# TC364_MainBoard_Core_V2_0.net
KiCad netlist of a schematic drawn in Altium Designer
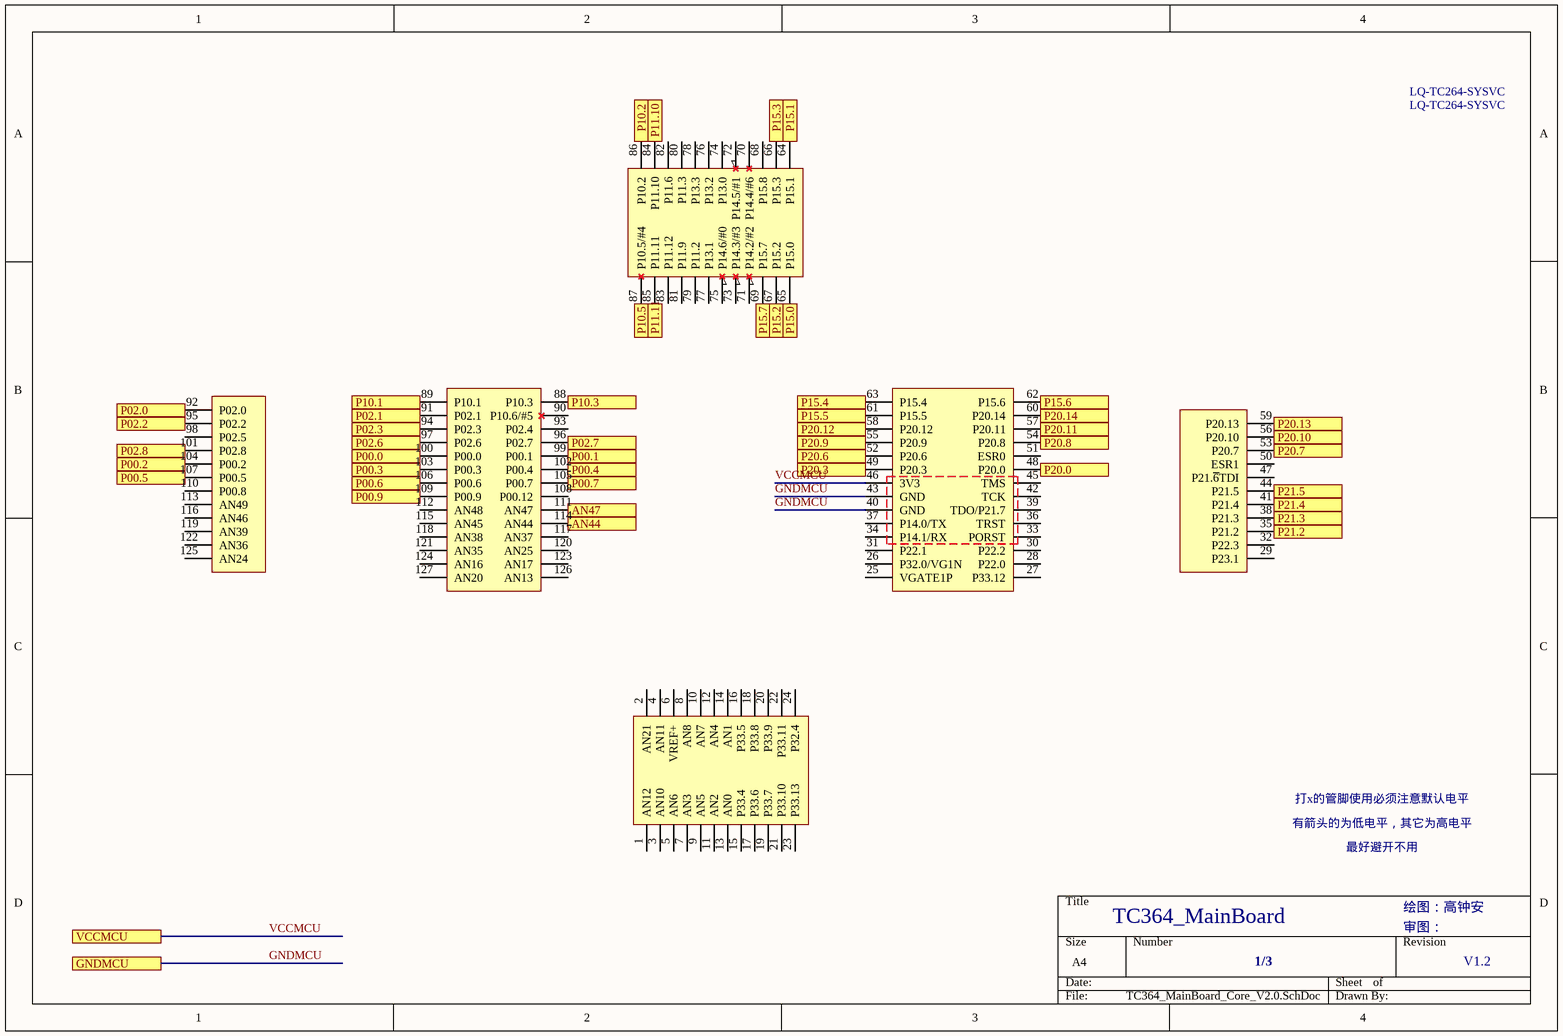
[diagram p0: TC364_MainBoard_Core_V2.0.SchDoc]

(export (version "E")
  (design (tool "Eeschema 10.0.6"))
  (components
    (comp (ref "LQ-TC264-SYSVC")
      (value "LQ-TC264-SYSVC")
      (footprint "TC364V1.2")
      (libsource (lib "LQ-TC264-SYSVC封装") (part "LQ-TC264-SYSVC"))
    )
  )
  (nets
    (net (code "1") (name "/AN44") (class "Default")
      (node (ref "LQ-TC264-SYSVC") (pin "114") (pinfunction "AN44_114") (pintype "passive"))
    )
    (net (code "2") (name "/AN47") (class "Default")
      (node (ref "LQ-TC264-SYSVC") (pin "111") (pinfunction "AN47_111") (pintype "passive"))
    )
    (net (code "3") (name "/GNDMCU") (class "Default")
      (node (ref "LQ-TC264-SYSVC") (pin "40") (pinfunction "GND_40") (pintype "passive"))
      (node (ref "LQ-TC264-SYSVC") (pin "43") (pinfunction "GND_43") (pintype "passive"))
    )
    (net (code "4") (name "/P00.0") (class "Default")
      (node (ref "LQ-TC264-SYSVC") (pin "100") (pinfunction "P00.0_100") (pintype "passive"))
    )
    (net (code "5") (name "/P00.1") (class "Default")
      (node (ref "LQ-TC264-SYSVC") (pin "99") (pinfunction "P00.1_99") (pintype "passive"))
    )
    (net (code "6") (name "/P00.2") (class "Default")
      (node (ref "LQ-TC264-SYSVC") (pin "104") (pinfunction "P00.2_104") (pintype "passive"))
    )
    (net (code "7") (name "/P00.3") (class "Default")
      (node (ref "LQ-TC264-SYSVC") (pin "103") (pinfunction "P00.3_103") (pintype "passive"))
    )
    (net (code "8") (name "/P00.4") (class "Default")
      (node (ref "LQ-TC264-SYSVC") (pin "102") (pinfunction "P00.4_102") (pintype "passive"))
    )
    (net (code "9") (name "/P00.5") (class "Default")
      (node (ref "LQ-TC264-SYSVC") (pin "107") (pinfunction "P00.5_107") (pintype "passive"))
    )
    (net (code "10") (name "/P00.6") (class "Default")
      (node (ref "LQ-TC264-SYSVC") (pin "106") (pinfunction "P00.6_106") (pintype "passive"))
    )
    (net (code "11") (name "/P00.7") (class "Default")
      (node (ref "LQ-TC264-SYSVC") (pin "105") (pinfunction "P00.7_105") (pintype "passive"))
    )
    (net (code "12") (name "/P00.9") (class "Default")
      (node (ref "LQ-TC264-SYSVC") (pin "109") (pinfunction "P00.9_109") (pintype "passive"))
    )
    (net (code "13") (name "/P02.0") (class "Default")
      (node (ref "LQ-TC264-SYSVC") (pin "92") (pinfunction "P02.0_92") (pintype "passive"))
    )
    (net (code "14") (name "/P02.1") (class "Default")
      (node (ref "LQ-TC264-SYSVC") (pin "91") (pinfunction "P02.1_91") (pintype "passive"))
    )
    (net (code "15") (name "/P02.2") (class "Default")
      (node (ref "LQ-TC264-SYSVC") (pin "95") (pinfunction "P02.2_95") (pintype "passive"))
    )
    (net (code "16") (name "/P02.3") (class "Default")
      (node (ref "LQ-TC264-SYSVC") (pin "94") (pinfunction "P02.3_94") (pintype "passive"))
    )
    (net (code "17") (name "/P02.6") (class "Default")
      (node (ref "LQ-TC264-SYSVC") (pin "97") (pinfunction "P02.6_97") (pintype "passive"))
    )
    (net (code "18") (name "/P02.7") (class "Default")
      (node (ref "LQ-TC264-SYSVC") (pin "96") (pinfunction "P02.7_96") (pintype "passive"))
    )
    (net (code "19") (name "/P02.8") (class "Default")
      (node (ref "LQ-TC264-SYSVC") (pin "101") (pinfunction "P02.8_101") (pintype "passive"))
    )
    (net (code "20") (name "/P10.1") (class "Default")
      (node (ref "LQ-TC264-SYSVC") (pin "89") (pinfunction "P10.1_89") (pintype "passive"))
    )
    (net (code "21") (name "/P10.2") (class "Default")
      (node (ref "LQ-TC264-SYSVC") (pin "86") (pinfunction "P10.2_86") (pintype "passive"))
    )
    (net (code "22") (name "/P10.3") (class "Default")
      (node (ref "LQ-TC264-SYSVC") (pin "88") (pinfunction "P10.3_88") (pintype "passive"))
    )
    (net (code "23") (name "/P10.5") (class "Default")
      (node (ref "LQ-TC264-SYSVC") (pin "87") (pinfunction "P10.5/#4_87") (pintype "passive"))
    )
    (net (code "24") (name "/P11.10") (class "Default")
      (node (ref "LQ-TC264-SYSVC") (pin "84") (pinfunction "P11.10_84") (pintype "passive"))
    )
    (net (code "25") (name "/P11.11") (class "Default")
      (node (ref "LQ-TC264-SYSVC") (pin "85") (pinfunction "P11.11_85") (pintype "passive"))
    )
    (net (code "26") (name "/P15.0") (class "Default")
      (node (ref "LQ-TC264-SYSVC") (pin "65") (pinfunction "P15.0_65") (pintype "passive"))
    )
    (net (code "27") (name "/P15.1") (class "Default")
      (node (ref "LQ-TC264-SYSVC") (pin "64") (pinfunction "P15.1_64") (pintype "passive"))
    )
    (net (code "28") (name "/P15.2") (class "Default")
      (node (ref "LQ-TC264-SYSVC") (pin "67") (pinfunction "P15.2_67") (pintype "passive"))
    )
    (net (code "29") (name "/P15.3") (class "Default")
      (node (ref "LQ-TC264-SYSVC") (pin "66") (pinfunction "P15.3_66") (pintype "passive"))
    )
    (net (code "30") (name "/P15.4") (class "Default")
      (node (ref "LQ-TC264-SYSVC") (pin "63") (pinfunction "P15.4_63") (pintype "passive"))
    )
    (net (code "31") (name "/P15.5") (class "Default")
      (node (ref "LQ-TC264-SYSVC") (pin "61") (pinfunction "P15.5_61") (pintype "passive"))
    )
    (net (code "32") (name "/P15.6") (class "Default")
      (node (ref "LQ-TC264-SYSVC") (pin "62") (pinfunction "P15.6_62") (pintype "passive"))
    )
    (net (code "33") (name "/P15.7") (class "Default")
      (node (ref "LQ-TC264-SYSVC") (pin "69") (pinfunction "P15.7_69") (pintype "passive"))
    )
    (net (code "34") (name "/P20.0") (class "Default")
      (node (ref "LQ-TC264-SYSVC") (pin "48") (pinfunction "P20.0_48") (pintype "passive"))
    )
    (net (code "35") (name "/P20.3") (class "Default")
      (node (ref "LQ-TC264-SYSVC") (pin "49") (pinfunction "P20.3_49") (pintype "passive"))
    )
    (net (code "36") (name "/P20.6") (class "Default")
      (node (ref "LQ-TC264-SYSVC") (pin "52") (pinfunction "P20.6_52") (pintype "passive"))
    )
    (net (code "37") (name "/P20.7") (class "Default")
      (node (ref "LQ-TC264-SYSVC") (pin "53") (pinfunction "P20.7_53") (pintype "passive"))
    )
    (net (code "38") (name "/P20.8") (class "Default")
      (node (ref "LQ-TC264-SYSVC") (pin "54") (pinfunction "P20.8_54") (pintype "passive"))
    )
    (net (code "39") (name "/P20.9") (class "Default")
      (node (ref "LQ-TC264-SYSVC") (pin "55") (pinfunction "P20.9_55") (pintype "passive"))
    )
    (net (code "40") (name "/P20.10") (class "Default")
      (node (ref "LQ-TC264-SYSVC") (pin "56") (pinfunction "P20.10_56") (pintype "passive"))
    )
    (net (code "41") (name "/P20.11") (class "Default")
      (node (ref "LQ-TC264-SYSVC") (pin "57") (pinfunction "P20.11_57") (pintype "passive"))
    )
    (net (code "42") (name "/P20.12") (class "Default")
      (node (ref "LQ-TC264-SYSVC") (pin "58") (pinfunction "P20.12_58") (pintype "passive"))
    )
    (net (code "43") (name "/P20.13") (class "Default")
      (node (ref "LQ-TC264-SYSVC") (pin "59") (pinfunction "P20.13_59") (pintype "passive"))
    )
    (net (code "44") (name "/P20.14") (class "Default")
      (node (ref "LQ-TC264-SYSVC") (pin "60") (pinfunction "P20.14_60") (pintype "passive"))
    )
    (net (code "45") (name "/P21.2") (class "Default")
      (node (ref "LQ-TC264-SYSVC") (pin "35") (pinfunction "P21.2_35") (pintype "passive"))
    )
    (net (code "46") (name "/P21.3") (class "Default")
      (node (ref "LQ-TC264-SYSVC") (pin "38") (pinfunction "P21.3_38") (pintype "passive"))
    )
    (net (code "47") (name "/P21.4") (class "Default")
      (node (ref "LQ-TC264-SYSVC") (pin "41") (pinfunction "P21.4_41") (pintype "passive"))
    )
    (net (code "48") (name "/P21.5") (class "Default")
      (node (ref "LQ-TC264-SYSVC") (pin "44") (pinfunction "P21.5_44") (pintype "passive"))
    )
    (net (code "49") (name "/VCCMCU") (class "Default")
      (node (ref "LQ-TC264-SYSVC") (pin "46") (pinfunction "3V3_46") (pintype "passive"))
    )
    (net (code "50") (name "unconnected-(LQ-TC264-SYSVC-AN0-Pad13)") (class "Default")
      (node (ref "LQ-TC264-SYSVC") (pin "13") (pinfunction "AN0_13") (pintype "passive"))
    )
    (net (code "51") (name "unconnected-(LQ-TC264-SYSVC-AN1-Pad14)") (class "Default")
      (node (ref "LQ-TC264-SYSVC") (pin "14") (pinfunction "AN1_14") (pintype "passive"))
    )
    (net (code "52") (name "unconnected-(LQ-TC264-SYSVC-AN2-Pad11)") (class "Default")
      (node (ref "LQ-TC264-SYSVC") (pin "11") (pinfunction "AN2_11") (pintype "passive"))
    )
    (net (code "53") (name "unconnected-(LQ-TC264-SYSVC-AN3-Pad7)") (class "Default")
      (node (ref "LQ-TC264-SYSVC") (pin "7") (pinfunction "AN3_7") (pintype "passive"))
    )
    (net (code "54") (name "unconnected-(LQ-TC264-SYSVC-AN4-Pad12)") (class "Default")
      (node (ref "LQ-TC264-SYSVC") (pin "12") (pinfunction "AN4_12") (pintype "passive"))
    )
    (net (code "55") (name "unconnected-(LQ-TC264-SYSVC-AN5-Pad9)") (class "Default")
      (node (ref "LQ-TC264-SYSVC") (pin "9") (pinfunction "AN5_9") (pintype "passive"))
    )
    (net (code "56") (name "unconnected-(LQ-TC264-SYSVC-AN6-Pad5)") (class "Default")
      (node (ref "LQ-TC264-SYSVC") (pin "5") (pinfunction "AN6_5") (pintype "passive"))
    )
    (net (code "57") (name "unconnected-(LQ-TC264-SYSVC-AN7-Pad10)") (class "Default")
      (node (ref "LQ-TC264-SYSVC") (pin "10") (pinfunction "AN7_10") (pintype "passive"))
    )
    (net (code "58") (name "unconnected-(LQ-TC264-SYSVC-AN8-Pad8)") (class "Default")
      (node (ref "LQ-TC264-SYSVC") (pin "8") (pinfunction "AN8_8") (pintype "passive"))
    )
    (net (code "59") (name "unconnected-(LQ-TC264-SYSVC-AN10-Pad3)") (class "Default")
      (node (ref "LQ-TC264-SYSVC") (pin "3") (pinfunction "AN10_3") (pintype "passive"))
    )
    (net (code "60") (name "unconnected-(LQ-TC264-SYSVC-AN11-Pad4)") (class "Default")
      (node (ref "LQ-TC264-SYSVC") (pin "4") (pinfunction "AN11_4") (pintype "passive"))
    )
    (net (code "61") (name "unconnected-(LQ-TC264-SYSVC-AN12-Pad1)") (class "Default")
      (node (ref "LQ-TC264-SYSVC") (pin "1") (pinfunction "AN12_1") (pintype "passive"))
    )
    (net (code "62") (name "unconnected-(LQ-TC264-SYSVC-AN13-Pad126)") (class "Default")
      (node (ref "LQ-TC264-SYSVC") (pin "126") (pinfunction "AN13_126") (pintype "passive"))
    )
    (net (code "63") (name "unconnected-(LQ-TC264-SYSVC-AN16-Pad124)") (class "Default")
      (node (ref "LQ-TC264-SYSVC") (pin "124") (pinfunction "AN16_124") (pintype "passive"))
    )
    (net (code "64") (name "unconnected-(LQ-TC264-SYSVC-AN17-Pad123)") (class "Default")
      (node (ref "LQ-TC264-SYSVC") (pin "123") (pinfunction "AN17_123") (pintype "passive"))
    )
    (net (code "65") (name "unconnected-(LQ-TC264-SYSVC-AN20-Pad127)") (class "Default")
      (node (ref "LQ-TC264-SYSVC") (pin "127") (pinfunction "AN20_127") (pintype "passive"))
    )
    (net (code "66") (name "unconnected-(LQ-TC264-SYSVC-AN21-Pad2)") (class "Default")
      (node (ref "LQ-TC264-SYSVC") (pin "2") (pinfunction "AN21_2") (pintype "passive"))
    )
    (net (code "67") (name "unconnected-(LQ-TC264-SYSVC-AN24-Pad125)") (class "Default")
      (node (ref "LQ-TC264-SYSVC") (pin "125") (pinfunction "AN24_125") (pintype "passive"))
    )
    (net (code "68") (name "unconnected-(LQ-TC264-SYSVC-AN25-Pad120)") (class "Default")
      (node (ref "LQ-TC264-SYSVC") (pin "120") (pinfunction "AN25_120") (pintype "passive"))
    )
    (net (code "69") (name "unconnected-(LQ-TC264-SYSVC-AN35-Pad121)") (class "Default")
      (node (ref "LQ-TC264-SYSVC") (pin "121") (pinfunction "AN35_121") (pintype "passive"))
    )
    (net (code "70") (name "unconnected-(LQ-TC264-SYSVC-AN36-Pad122)") (class "Default")
      (node (ref "LQ-TC264-SYSVC") (pin "122") (pinfunction "AN36_122") (pintype "passive"))
    )
    (net (code "71") (name "unconnected-(LQ-TC264-SYSVC-AN37-Pad117)") (class "Default")
      (node (ref "LQ-TC264-SYSVC") (pin "117") (pinfunction "AN37_117") (pintype "passive"))
    )
    (net (code "72") (name "unconnected-(LQ-TC264-SYSVC-AN38-Pad118)") (class "Default")
      (node (ref "LQ-TC264-SYSVC") (pin "118") (pinfunction "AN38_118") (pintype "passive"))
    )
    (net (code "73") (name "unconnected-(LQ-TC264-SYSVC-AN39-Pad119)") (class "Default")
      (node (ref "LQ-TC264-SYSVC") (pin "119") (pinfunction "AN39_119") (pintype "passive"))
    )
    (net (code "74") (name "unconnected-(LQ-TC264-SYSVC-AN45-Pad115)") (class "Default")
      (node (ref "LQ-TC264-SYSVC") (pin "115") (pinfunction "AN45_115") (pintype "passive"))
    )
    (net (code "75") (name "unconnected-(LQ-TC264-SYSVC-AN46-Pad116)") (class "Default")
      (node (ref "LQ-TC264-SYSVC") (pin "116") (pinfunction "AN46_116") (pintype "passive"))
    )
    (net (code "76") (name "unconnected-(LQ-TC264-SYSVC-AN48-Pad112)") (class "Default")
      (node (ref "LQ-TC264-SYSVC") (pin "112") (pinfunction "AN48_112") (pintype "passive"))
    )
    (net (code "77") (name "unconnected-(LQ-TC264-SYSVC-AN49-Pad113)") (class "Default")
      (node (ref "LQ-TC264-SYSVC") (pin "113") (pinfunction "AN49_113") (pintype "passive"))
    )
    (net (code "78") (name "unconnected-(LQ-TC264-SYSVC-ESR0-Pad51)") (class "Default")
      (node (ref "LQ-TC264-SYSVC") (pin "51") (pinfunction "ESR0_51") (pintype "passive"))
    )
    (net (code "79") (name "unconnected-(LQ-TC264-SYSVC-ESR1-Pad50)") (class "Default")
      (node (ref "LQ-TC264-SYSVC") (pin "50") (pinfunction "ESR1_50") (pintype "passive"))
    )
    (net (code "80") (name "unconnected-(LQ-TC264-SYSVC-P00.8-Pad110)") (class "Default")
      (node (ref "LQ-TC264-SYSVC") (pin "110") (pinfunction "P00.8_110") (pintype "passive"))
    )
    (net (code "81") (name "unconnected-(LQ-TC264-SYSVC-P00.12-Pad108)") (class "Default")
      (node (ref "LQ-TC264-SYSVC") (pin "108") (pinfunction "P00.12_108") (pintype "passive"))
    )
    (net (code "82") (name "unconnected-(LQ-TC264-SYSVC-P02.4-Pad93)") (class "Default")
      (node (ref "LQ-TC264-SYSVC") (pin "93") (pinfunction "P02.4_93") (pintype "passive"))
    )
    (net (code "83") (name "unconnected-(LQ-TC264-SYSVC-P02.5-Pad98)") (class "Default")
      (node (ref "LQ-TC264-SYSVC") (pin "98") (pinfunction "P02.5_98") (pintype "passive"))
    )
    (net (code "84") (name "unconnected-(LQ-TC264-SYSVC-P10.6{slash}#5-Pad90)") (class "Default")
      (node (ref "LQ-TC264-SYSVC") (pin "90") (pinfunction "P10.6/#5_90") (pintype "passive"))
    )
    (net (code "85") (name "unconnected-(LQ-TC264-SYSVC-P11.2-Pad79)") (class "Default")
      (node (ref "LQ-TC264-SYSVC") (pin "79") (pinfunction "P11.2_79") (pintype "passive"))
    )
    (net (code "86") (name "unconnected-(LQ-TC264-SYSVC-P11.3-Pad80)") (class "Default")
      (node (ref "LQ-TC264-SYSVC") (pin "80") (pinfunction "P11.3_80") (pintype "passive"))
    )
    (net (code "87") (name "unconnected-(LQ-TC264-SYSVC-P11.6-Pad82)") (class "Default")
      (node (ref "LQ-TC264-SYSVC") (pin "82") (pinfunction "P11.6_82") (pintype "passive"))
    )
    (net (code "88") (name "unconnected-(LQ-TC264-SYSVC-P11.9-Pad81)") (class "Default")
      (node (ref "LQ-TC264-SYSVC") (pin "81") (pinfunction "P11.9_81") (pintype "passive"))
    )
    (net (code "89") (name "unconnected-(LQ-TC264-SYSVC-P11.12-Pad83)") (class "Default")
      (node (ref "LQ-TC264-SYSVC") (pin "83") (pinfunction "P11.12_83") (pintype "passive"))
    )
    (net (code "90") (name "unconnected-(LQ-TC264-SYSVC-P13.0-Pad74)") (class "Default")
      (node (ref "LQ-TC264-SYSVC") (pin "74") (pinfunction "P13.0_74") (pintype "passive"))
    )
    (net (code "91") (name "unconnected-(LQ-TC264-SYSVC-P13.1-Pad77)") (class "Default")
      (node (ref "LQ-TC264-SYSVC") (pin "77") (pinfunction "P13.1_77") (pintype "passive"))
    )
    (net (code "92") (name "unconnected-(LQ-TC264-SYSVC-P13.2-Pad76)") (class "Default")
      (node (ref "LQ-TC264-SYSVC") (pin "76") (pinfunction "P13.2_76") (pintype "passive"))
    )
    (net (code "93") (name "unconnected-(LQ-TC264-SYSVC-P13.3-Pad78)") (class "Default")
      (node (ref "LQ-TC264-SYSVC") (pin "78") (pinfunction "P13.3_78") (pintype "passive"))
    )
    (net (code "94") (name "unconnected-(LQ-TC264-SYSVC-P14.0{slash}TX-Pad37)") (class "Default")
      (node (ref "LQ-TC264-SYSVC") (pin "37") (pinfunction "P14.0/TX_37") (pintype "passive"))
    )
    (net (code "95") (name "unconnected-(LQ-TC264-SYSVC-P14.1{slash}RX-Pad34)") (class "Default")
      (node (ref "LQ-TC264-SYSVC") (pin "34") (pinfunction "P14.1/RX_34") (pintype "passive"))
    )
    (net (code "96") (name "unconnected-(LQ-TC264-SYSVC-P14.2{slash}#2-Pad71)") (class "Default")
      (node (ref "LQ-TC264-SYSVC") (pin "71") (pinfunction "P14.2/#2_71") (pintype "passive"))
    )
    (net (code "97") (name "unconnected-(LQ-TC264-SYSVC-P14.3{slash}#3-Pad73)") (class "Default")
      (node (ref "LQ-TC264-SYSVC") (pin "73") (pinfunction "P14.3/#3_73") (pintype "passive"))
    )
    (net (code "98") (name "unconnected-(LQ-TC264-SYSVC-P14.4{slash}#6-Pad70)") (class "Default")
      (node (ref "LQ-TC264-SYSVC") (pin "70") (pinfunction "P14.4/#6_70") (pintype "passive"))
    )
    (net (code "99") (name "unconnected-(LQ-TC264-SYSVC-P14.5{slash}#1-Pad72)") (class "Default")
      (node (ref "LQ-TC264-SYSVC") (pin "72") (pinfunction "P14.5/#1_72") (pintype "passive"))
    )
    (net (code "100") (name "unconnected-(LQ-TC264-SYSVC-P14.6{slash}#0-Pad75)") (class "Default")
      (node (ref "LQ-TC264-SYSVC") (pin "75") (pinfunction "P14.6/#0_75") (pintype "passive"))
    )
    (net (code "101") (name "unconnected-(LQ-TC264-SYSVC-P15.8-Pad68)") (class "Default")
      (node (ref "LQ-TC264-SYSVC") (pin "68") (pinfunction "P15.8_68") (pintype "passive"))
    )
    (net (code "102") (name "unconnected-(LQ-TC264-SYSVC-P21.~{6}TDI-Pad47)") (class "Default")
      (node (ref "LQ-TC264-SYSVC") (pin "47") (pinfunction "P21.~{6}TDI_47") (pintype "passive"))
    )
    (net (code "103") (name "unconnected-(LQ-TC264-SYSVC-P22.0-Pad28)") (class "Default")
      (node (ref "LQ-TC264-SYSVC") (pin "28") (pinfunction "P22.0_28") (pintype "passive"))
    )
    (net (code "104") (name "unconnected-(LQ-TC264-SYSVC-P22.1-Pad31)") (class "Default")
      (node (ref "LQ-TC264-SYSVC") (pin "31") (pinfunction "P22.1_31") (pintype "passive"))
    )
    (net (code "105") (name "unconnected-(LQ-TC264-SYSVC-P22.2-Pad30)") (class "Default")
      (node (ref "LQ-TC264-SYSVC") (pin "30") (pinfunction "P22.2_30") (pintype "passive"))
    )
    (net (code "106") (name "unconnected-(LQ-TC264-SYSVC-P22.3-Pad32)") (class "Default")
      (node (ref "LQ-TC264-SYSVC") (pin "32") (pinfunction "P22.3_32") (pintype "passive"))
    )
    (net (code "107") (name "unconnected-(LQ-TC264-SYSVC-P23.1-Pad29)") (class "Default")
      (node (ref "LQ-TC264-SYSVC") (pin "29") (pinfunction "P23.1_29") (pintype "passive"))
    )
    (net (code "108") (name "unconnected-(LQ-TC264-SYSVC-P32.0{slash}VG1N-Pad26)") (class "Default")
      (node (ref "LQ-TC264-SYSVC") (pin "26") (pinfunction "P32.0/VG1N_26") (pintype "passive"))
    )
    (net (code "109") (name "unconnected-(LQ-TC264-SYSVC-P32.4-Pad24)") (class "Default")
      (node (ref "LQ-TC264-SYSVC") (pin "24") (pinfunction "P32.4_24") (pintype "passive"))
    )
    (net (code "110") (name "unconnected-(LQ-TC264-SYSVC-P33.4-Pad15)") (class "Default")
      (node (ref "LQ-TC264-SYSVC") (pin "15") (pinfunction "P33.4_15") (pintype "passive"))
    )
    (net (code "111") (name "unconnected-(LQ-TC264-SYSVC-P33.5-Pad16)") (class "Default")
      (node (ref "LQ-TC264-SYSVC") (pin "16") (pinfunction "P33.5_16") (pintype "passive"))
    )
    (net (code "112") (name "unconnected-(LQ-TC264-SYSVC-P33.6-Pad17)") (class "Default")
      (node (ref "LQ-TC264-SYSVC") (pin "17") (pinfunction "P33.6_17") (pintype "passive"))
    )
    (net (code "113") (name "unconnected-(LQ-TC264-SYSVC-P33.7-Pad19)") (class "Default")
      (node (ref "LQ-TC264-SYSVC") (pin "19") (pinfunction "P33.7_19") (pintype "passive"))
    )
    (net (code "114") (name "unconnected-(LQ-TC264-SYSVC-P33.8-Pad18)") (class "Default")
      (node (ref "LQ-TC264-SYSVC") (pin "18") (pinfunction "P33.8_18") (pintype "passive"))
    )
    (net (code "115") (name "unconnected-(LQ-TC264-SYSVC-P33.9-Pad20)") (class "Default")
      (node (ref "LQ-TC264-SYSVC") (pin "20") (pinfunction "P33.9_20") (pintype "passive"))
    )
    (net (code "116") (name "unconnected-(LQ-TC264-SYSVC-P33.10-Pad21)") (class "Default")
      (node (ref "LQ-TC264-SYSVC") (pin "21") (pinfunction "P33.10_21") (pintype "passive"))
    )
    (net (code "117") (name "unconnected-(LQ-TC264-SYSVC-P33.11-Pad22)") (class "Default")
      (node (ref "LQ-TC264-SYSVC") (pin "22") (pinfunction "P33.11_22") (pintype "passive"))
    )
    (net (code "118") (name "unconnected-(LQ-TC264-SYSVC-P33.12-Pad27)") (class "Default")
      (node (ref "LQ-TC264-SYSVC") (pin "27") (pinfunction "P33.12_27") (pintype "passive"))
    )
    (net (code "119") (name "unconnected-(LQ-TC264-SYSVC-P33.13-Pad23)") (class "Default")
      (node (ref "LQ-TC264-SYSVC") (pin "23") (pinfunction "P33.13_23") (pintype "passive"))
    )
    (net (code "120") (name "unconnected-(LQ-TC264-SYSVC-PORST-Pad33)") (class "Default")
      (node (ref "LQ-TC264-SYSVC") (pin "33") (pinfunction "PORST_33") (pintype "passive"))
    )
    (net (code "121") (name "unconnected-(LQ-TC264-SYSVC-TCK-Pad42)") (class "Default")
      (node (ref "LQ-TC264-SYSVC") (pin "42") (pinfunction "TCK_42") (pintype "passive"))
    )
    (net (code "122") (name "unconnected-(LQ-TC264-SYSVC-TDO{slash}P21.7-Pad39)") (class "Default")
      (node (ref "LQ-TC264-SYSVC") (pin "39") (pinfunction "TDO/P21.7_39") (pintype "passive"))
    )
    (net (code "123") (name "unconnected-(LQ-TC264-SYSVC-TMS-Pad45)") (class "Default")
      (node (ref "LQ-TC264-SYSVC") (pin "45") (pinfunction "TMS_45") (pintype "passive"))
    )
    (net (code "124") (name "unconnected-(LQ-TC264-SYSVC-TRST-Pad36)") (class "Default")
      (node (ref "LQ-TC264-SYSVC") (pin "36") (pinfunction "TRST_36") (pintype "passive"))
    )
    (net (code "125") (name "unconnected-(LQ-TC264-SYSVC-VGATE1P-Pad25)") (class "Default")
      (node (ref "LQ-TC264-SYSVC") (pin "25") (pinfunction "VGATE1P_25") (pintype "passive"))
    )
    (net (code "126") (name "unconnected-(LQ-TC264-SYSVC-VREF+-Pad6)") (class "Default")
      (node (ref "LQ-TC264-SYSVC") (pin "6") (pinfunction "VREF+_6") (pintype "passive"))
    )
  )
)
